# Interrupt.net
KiCad netlist of a schematic drawn in EAGLE
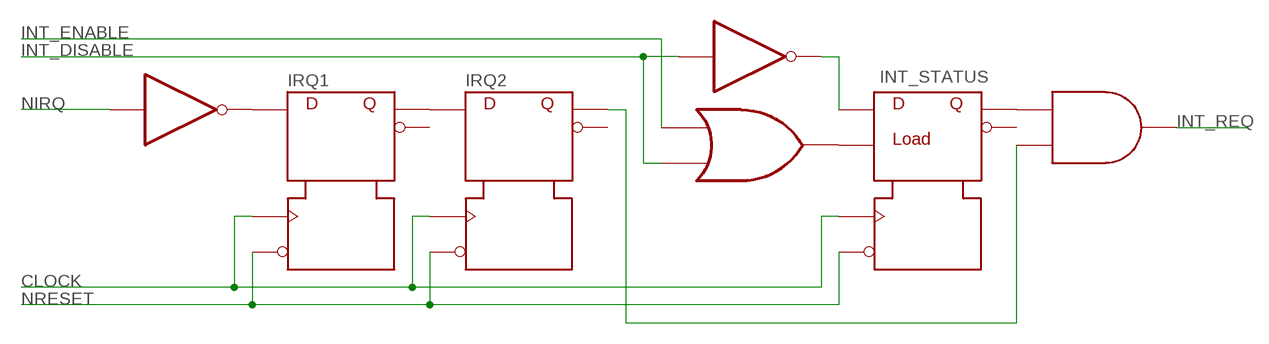
[diagram p0: schematic, sheet 1]

(export (version "E")
  (design (tool "Eeschema 10.0.6"))
  (components
    (comp (ref "AND2_1")
      (value "AND2")
      (footprint "eagle-import:3PIN")
      (libsource (lib "eagle-import") (part "AND2"))
    )
    (comp (ref "INT_STATUS")
      (value "SCANREG")
      (footprint "eagle-import:6PIN")
      (libsource (lib "eagle-import") (part "SCANREG"))
    )
    (comp (ref "INV_1")
      (value "INV")
      (footprint "eagle-import:3PIN")
      (libsource (lib "eagle-import") (part "INV"))
    )
    (comp (ref "INV_2")
      (value "INV")
      (footprint "eagle-import:3PIN")
      (libsource (lib "eagle-import") (part "INV"))
    )
    (comp (ref "IRQ1")
      (value "SCANDTYPE")
      (footprint "eagle-import:5PIN")
      (libsource (lib "eagle-import") (part "SCANDTYPE"))
    )
    (comp (ref "IRQ2")
      (value "SCANDTYPE")
      (footprint "eagle-import:5PIN")
      (libsource (lib "eagle-import") (part "SCANDTYPE"))
    )
    (comp (ref "OR2_1")
      (value "OR2")
      (footprint "eagle-import:3PIN")
      (libsource (lib "eagle-import") (part "OR2"))
    )
  )
  (nets
    (net (code "1") (name "/CLOCK") (class "Default")
      (node (ref "INT_STATUS") (pin "P$1") (pinfunction "CLOCK_P$1") (pintype "bidirectional"))
      (node (ref "IRQ1") (pin "P$1") (pinfunction "CLOCK_P$1") (pintype "bidirectional"))
      (node (ref "IRQ2") (pin "P$1") (pinfunction "CLOCK_P$1") (pintype "bidirectional"))
    )
    (net (code "2") (name "/INT_DISABLE") (class "Default")
      (node (ref "INV_2") (pin "P$1") (pinfunction "I_P$1") (pintype "input"))
      (node (ref "OR2_1") (pin "P$2") (pinfunction "I1_P$2") (pintype "input"))
    )
    (net (code "3") (name "/INT_ENABLE") (class "Default")
      (node (ref "OR2_1") (pin "P$1") (pinfunction "I0_P$1") (pintype "input"))
    )
    (net (code "4") (name "/INT_REQ") (class "Default")
      (node (ref "AND2_1") (pin "P$3") (pinfunction "O_P$3") (pintype "output"))
    )
    (net (code "5") (name "/NIRQ") (class "Default")
      (node (ref "INV_1") (pin "P$1") (pinfunction "I_P$1") (pintype "input"))
    )
    (net (code "6") (name "/NRESET") (class "Default")
      (node (ref "INT_STATUS") (pin "P$5") (pinfunction "NRESET_P$5") (pintype "bidirectional"))
      (node (ref "IRQ1") (pin "P$4") (pinfunction "NRESET_P$4") (pintype "bidirectional"))
      (node (ref "IRQ2") (pin "P$4") (pinfunction "NRESET_P$4") (pintype "bidirectional"))
    )
    (net (code "7") (name "Net-(AND2_1-A)") (class "Default")
      (node (ref "AND2_1") (pin "P$1") (pinfunction "A_P$1") (pintype "input"))
      (node (ref "INT_STATUS") (pin "P$6") (pinfunction "Q_P$6") (pintype "bidirectional"))
    )
    (net (code "8") (name "Net-(AND2_1-I1)") (class "Default")
      (node (ref "AND2_1") (pin "P$2") (pinfunction "I1_P$2") (pintype "input"))
      (node (ref "IRQ2") (pin "P$5") (pinfunction "Q_P$5") (pintype "bidirectional"))
    )
    (net (code "9") (name "Net-(INT_STATUS-D)") (class "Default")
      (node (ref "INT_STATUS") (pin "P$2") (pinfunction "D_P$2") (pintype "bidirectional"))
      (node (ref "INV_2") (pin "P$2") (pinfunction "O_P$2") (pintype "open_collector"))
    )
    (net (code "10") (name "Net-(INT_STATUS-LOAD)") (class "Default")
      (node (ref "INT_STATUS") (pin "P$3") (pinfunction "LOAD_P$3") (pintype "bidirectional"))
      (node (ref "OR2_1") (pin "P$3") (pinfunction "O_P$3") (pintype "output"))
    )
    (net (code "11") (name "Net-(INV_1-O)") (class "Default")
      (node (ref "INV_1") (pin "P$2") (pinfunction "O_P$2") (pintype "open_collector"))
      (node (ref "IRQ1") (pin "P$2") (pinfunction "D_P$2") (pintype "bidirectional"))
    )
    (net (code "12") (name "Net-(IRQ1-Q)") (class "Default")
      (node (ref "IRQ1") (pin "P$5") (pinfunction "Q_P$5") (pintype "bidirectional"))
      (node (ref "IRQ2") (pin "P$2") (pinfunction "D_P$2") (pintype "bidirectional"))
    )
    (net (code "13") (name "unconnected-(INT_STATUS-NQ-PadP$4)") (class "Default")
      (node (ref "INT_STATUS") (pin "P$4") (pinfunction "NQ_P$4") (pintype "bidirectional"))
    )
    (net (code "14") (name "unconnected-(IRQ1-NQ-PadP$3)") (class "Default")
      (node (ref "IRQ1") (pin "P$3") (pinfunction "NQ_P$3") (pintype "bidirectional"))
    )
    (net (code "15") (name "unconnected-(IRQ2-NQ-PadP$3)") (class "Default")
      (node (ref "IRQ2") (pin "P$3") (pinfunction "NQ_P$3") (pintype "bidirectional"))
    )
  )
)
